# OSO-ALMO-A1-01.net
KiCad netlist of a schematic drawn in EAGLE
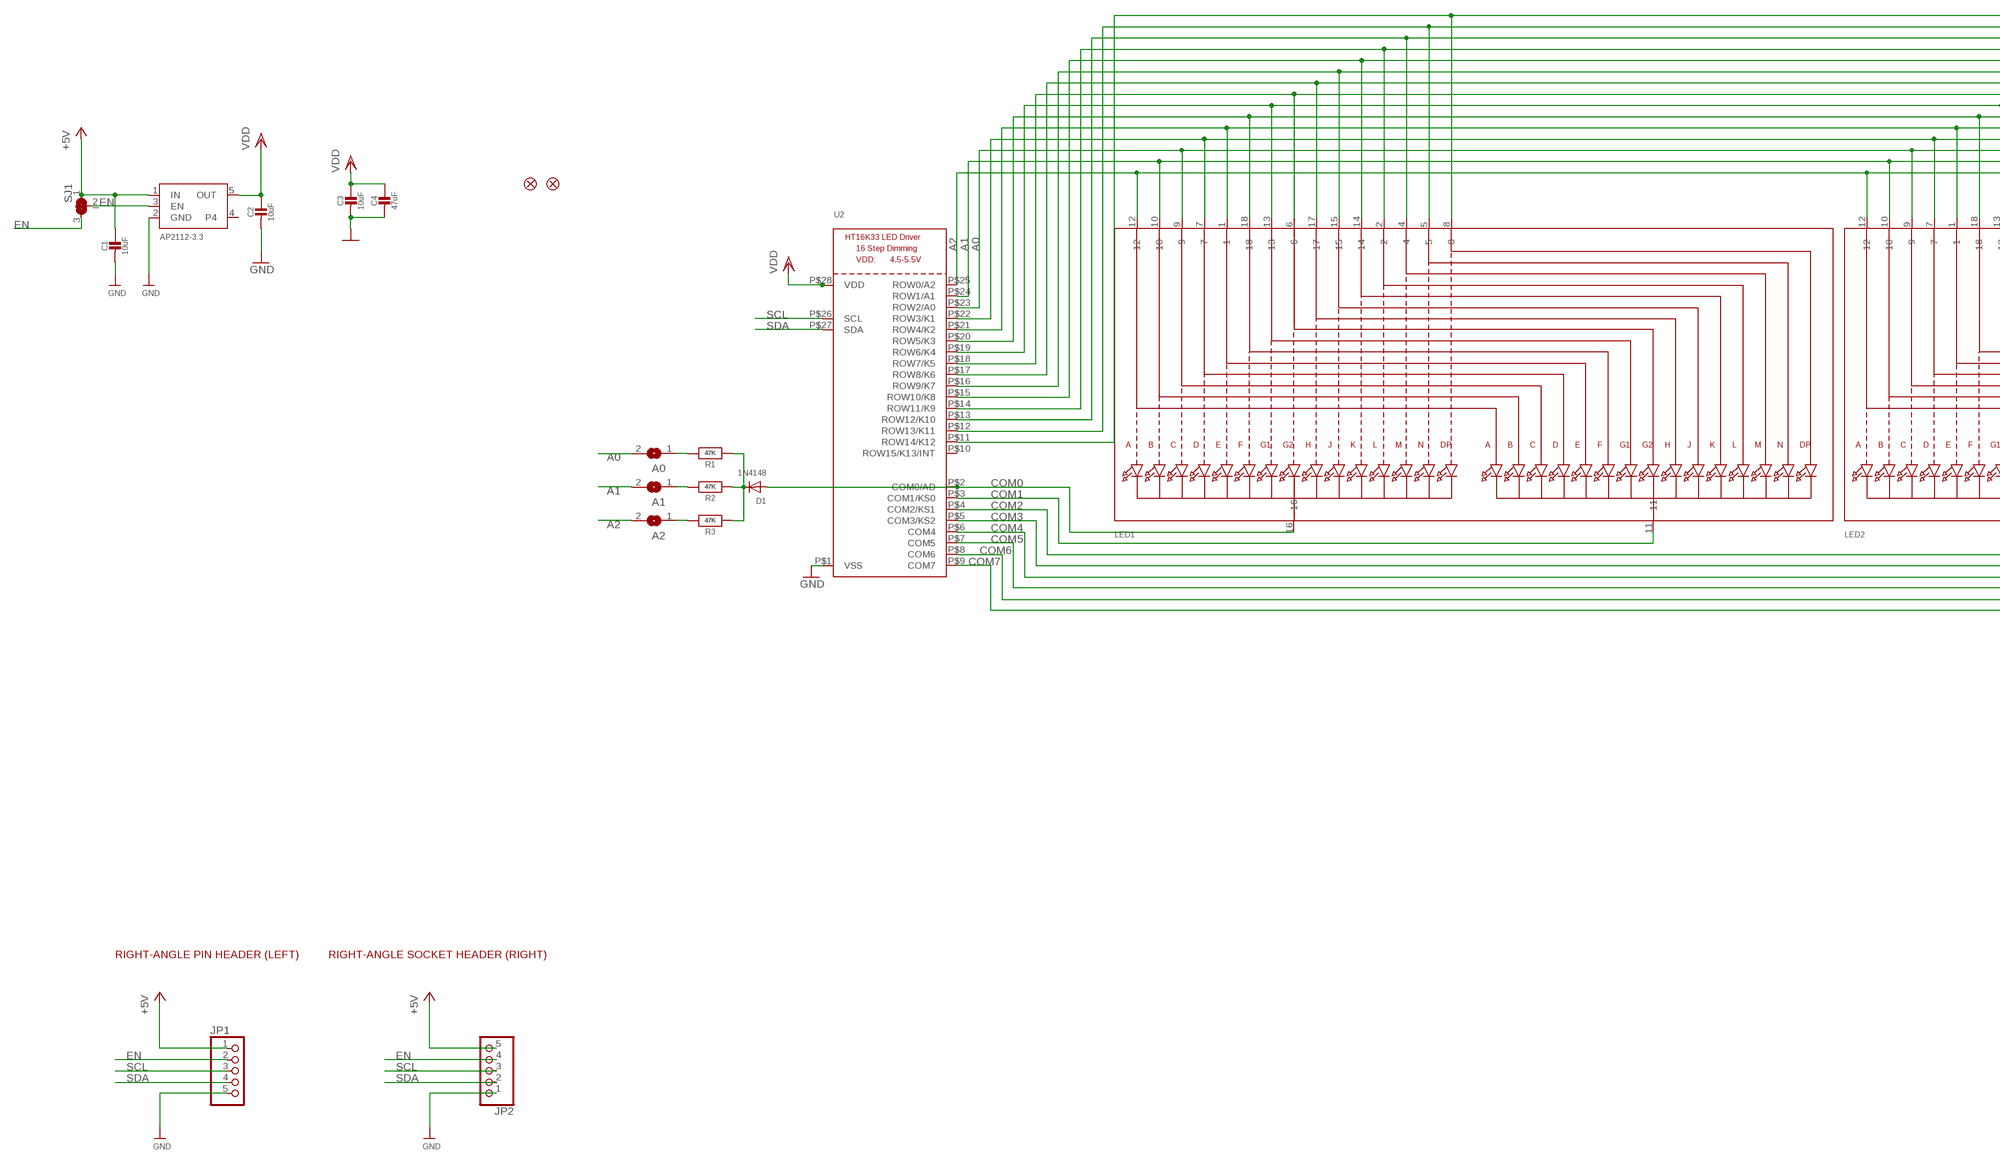
[diagram p0: schematic, sheet 1, part 1 of 2]
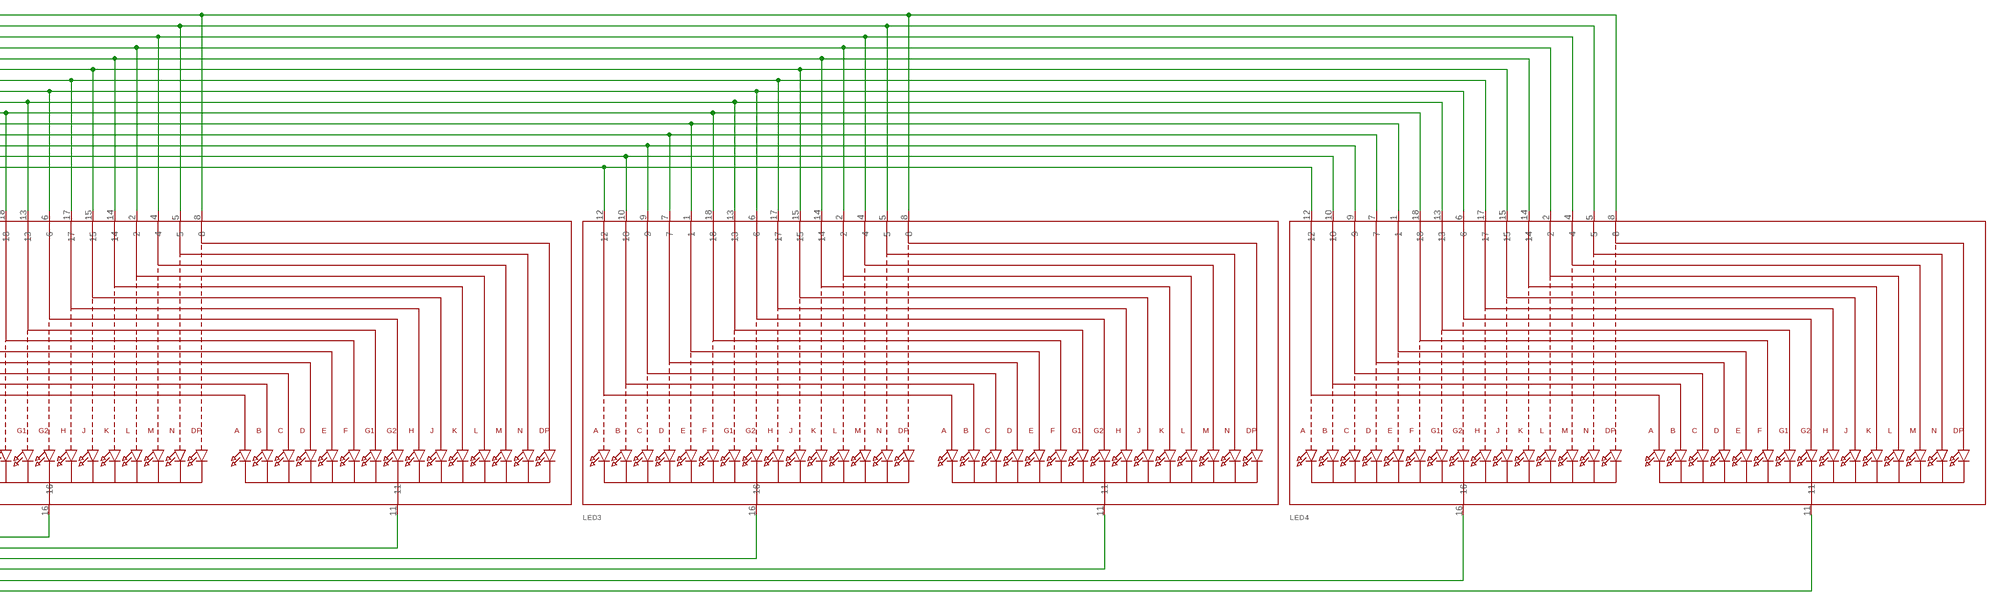
[diagram p1: schematic, sheet 1, part 2 of 2]

(export (version "E")
  (design (tool "Eeschema 10.0.6"))
  (components
    (comp (ref "A0")
      (value "SOLDERJUMPERREFLOW_NOPASTE")
      (footprint "eagle-import:SOLDERJUMPER_REFLOW_NOPASTE")
      (libsource (lib "eagle-import") (part "SOLDERJUMPERREFLOW_NOPASTE"))
    )
    (comp (ref "A1")
      (value "SOLDERJUMPERREFLOW_NOPASTE")
      (footprint "eagle-import:SOLDERJUMPER_REFLOW_NOPASTE")
      (libsource (lib "eagle-import") (part "SOLDERJUMPERREFLOW_NOPASTE"))
    )
    (comp (ref "A2")
      (value "SOLDERJUMPERREFLOW_NOPASTE")
      (footprint "eagle-import:SOLDERJUMPER_REFLOW_NOPASTE")
      (libsource (lib "eagle-import") (part "SOLDERJUMPERREFLOW_NOPASTE"))
    )
    (comp (ref "C1")
      (value "10uF")
      (footprint "eagle-import:0805-NO")
      (libsource (lib "eagle-import") (part "CAP_CERAMIC0805-NOOUTLINE"))
    )
    (comp (ref "C2")
      (value "10uF")
      (footprint "eagle-import:0805-NO")
      (libsource (lib "eagle-import") (part "CAP_CERAMIC0805-NOOUTLINE"))
    )
    (comp (ref "C3")
      (value "10uF")
      (footprint "eagle-import:0805-NO")
      (libsource (lib "eagle-import") (part "CAP_CERAMIC0805-NOOUTLINE"))
    )
    (comp (ref "C4")
      (value "47uF")
      (footprint "eagle-import:0805-NO")
      (libsource (lib "eagle-import") (part "CAP_CERAMIC0805-NOOUTLINE"))
    )
    (comp (ref "D1")
      (value "1N4148")
      (footprint "eagle-import:SOD-123FL")
      (libsource (lib "eagle-import") (part "DIODE_SOD-123FL"))
    )
    (comp (ref "JP1")
      (value "PINHD-1X5/90")
      (footprint "eagle-import:1X05_90")
      (libsource (lib "eagle-import") (part "PINHD-1X5/90"))
    )
    (comp (ref "JP2")
      (value "PINHD-1X5/90")
      (footprint "eagle-import:1X05_90")
      (libsource (lib "eagle-import") (part "PINHD-1X5/90"))
    )
    (comp (ref "LED1")
      (value "DISP_SEGMENT_STARBURST_DUAL_COMMONCATHODE")
      (footprint "eagle-import:SEGMENT_STARTBUST_DUAL_KWA-541CBB")
      (libsource (lib "eagle-import") (part "DISP_SEGMENT_STARBURST_DUAL_COMMONCATHODE"))
    )
    (comp (ref "LED2")
      (value "DISP_SEGMENT_STARBURST_DUAL_COMMONCATHODE")
      (footprint "eagle-import:SEGMENT_STARTBUST_DUAL_KWA-541CBB")
      (libsource (lib "eagle-import") (part "DISP_SEGMENT_STARBURST_DUAL_COMMONCATHODE"))
    )
    (comp (ref "LED3")
      (value "DISP_SEGMENT_STARBURST_DUAL_COMMONCATHODE")
      (footprint "eagle-import:SEGMENT_STARTBUST_DUAL_KWA-541CBB")
      (libsource (lib "eagle-import") (part "DISP_SEGMENT_STARBURST_DUAL_COMMONCATHODE"))
    )
    (comp (ref "LED4")
      (value "DISP_SEGMENT_STARBURST_DUAL_COMMONCATHODE")
      (footprint "eagle-import:SEGMENT_STARTBUST_DUAL_KWA-541CBB")
      (libsource (lib "eagle-import") (part "DISP_SEGMENT_STARBURST_DUAL_COMMONCATHODE"))
    )
    (comp (ref "R1")
      (value "47K")
      (footprint "eagle-import:0805-NO")
      (libsource (lib "eagle-import") (part "RESISTOR0805_NOOUTLINE"))
    )
    (comp (ref "R2")
      (value "47K")
      (footprint "eagle-import:0805-NO")
      (libsource (lib "eagle-import") (part "RESISTOR0805_NOOUTLINE"))
    )
    (comp (ref "R3")
      (value "47K")
      (footprint "eagle-import:0805-NO")
      (libsource (lib "eagle-import") (part "RESISTOR0805_NOOUTLINE"))
    )
    (comp (ref "SJ1")
      (value "SOLDERJUMPER_2WAY")
      (footprint "eagle-import:SOLDERJUMPER_2WAY_OPEN_NOPASTE")
      (libsource (lib "eagle-import") (part "SOLDERJUMPER_2WAY"))
    )
    (comp (ref "U$1")
      (value "FIDUCIAL\"\"")
      (footprint "eagle-import:FIDUCIAL_1MM")
      (libsource (lib "eagle-import") (part "FIDUCIAL{dblquote}{dblquote}"))
    )
    (comp (ref "U$2")
      (value "FIDUCIAL\"\"")
      (footprint "eagle-import:FIDUCIAL_1MM")
      (libsource (lib "eagle-import") (part "FIDUCIAL{dblquote}{dblquote}"))
    )
    (comp (ref "U1")
      (value "AP2112-3.3")
      (footprint "eagle-import:SOT23-5")
      (libsource (lib "eagle-import") (part "VREG_SOT23-5"))
    )
    (comp (ref "U2")
      (value "HT16K33_SOP28_SKINNY")
      (footprint "eagle-import:SOP28_300MIL_SKINNY")
      (libsource (lib "eagle-import") (part "HT16K33_SOP28_SKINNY"))
    )
  )
  (nets
    (net (code "1") (name "+5V") (class "Default")
      (node (ref "C1") (pin "1") (pinfunction "1_1") (pintype "passive"))
      (node (ref "JP1") (pin "1") (pinfunction "1_1") (pintype "passive"))
      (node (ref "JP2") (pin "5") (pinfunction "5_5") (pintype "passive"))
      (node (ref "SJ1") (pin "1") (pinfunction "1_1") (pintype "passive"))
      (node (ref "U1") (pin "1") (pinfunction "IN_1") (pintype "power_in"))
    )
    (net (code "2") (name "/A0") (class "Default")
      (node (ref "A0") (pin "2") (pinfunction "2_2") (pintype "passive"))
      (node (ref "LED1") (pin "9") (pinfunction "9_9") (pintype "bidirectional"))
      (node (ref "LED2") (pin "9") (pinfunction "9_9") (pintype "bidirectional"))
      (node (ref "LED3") (pin "9") (pinfunction "9_9") (pintype "bidirectional"))
      (node (ref "LED4") (pin "9") (pinfunction "9_9") (pintype "bidirectional"))
      (node (ref "U2") (pin "P$23") (pinfunction "ROW2/A0_P$23") (pintype "bidirectional"))
    )
    (net (code "3") (name "/A1") (class "Default")
      (node (ref "A1") (pin "2") (pinfunction "2_2") (pintype "passive"))
      (node (ref "LED1") (pin "10") (pinfunction "10_10") (pintype "bidirectional"))
      (node (ref "LED2") (pin "10") (pinfunction "10_10") (pintype "bidirectional"))
      (node (ref "LED3") (pin "10") (pinfunction "10_10") (pintype "bidirectional"))
      (node (ref "LED4") (pin "10") (pinfunction "10_10") (pintype "bidirectional"))
      (node (ref "U2") (pin "P$24") (pinfunction "ROW1/A1_P$24") (pintype "bidirectional"))
    )
    (net (code "4") (name "/A2") (class "Default")
      (node (ref "A2") (pin "2") (pinfunction "2_2") (pintype "passive"))
      (node (ref "LED1") (pin "12") (pinfunction "12_12") (pintype "bidirectional"))
      (node (ref "LED2") (pin "12") (pinfunction "12_12") (pintype "bidirectional"))
      (node (ref "LED3") (pin "12") (pinfunction "12_12") (pintype "bidirectional"))
      (node (ref "LED4") (pin "12") (pinfunction "12_12") (pintype "bidirectional"))
      (node (ref "U2") (pin "P$25") (pinfunction "ROW0/A2_P$25") (pintype "bidirectional"))
    )
    (net (code "5") (name "/COM0") (class "Default")
      (node (ref "D1") (pin "A") (pinfunction "A_A") (pintype "passive"))
      (node (ref "LED1") (pin "16") (pinfunction "16_16") (pintype "bidirectional"))
      (node (ref "U2") (pin "P$2") (pinfunction "COM0/AD_P$2") (pintype "bidirectional"))
    )
    (net (code "6") (name "/COM1") (class "Default")
      (node (ref "LED1") (pin "11") (pinfunction "11_11") (pintype "bidirectional"))
      (node (ref "U2") (pin "P$3") (pinfunction "COM1/KS0_P$3") (pintype "bidirectional"))
    )
    (net (code "7") (name "/COM2") (class "Default")
      (node (ref "LED2") (pin "16") (pinfunction "16_16") (pintype "bidirectional"))
      (node (ref "U2") (pin "P$4") (pinfunction "COM2/KS1_P$4") (pintype "bidirectional"))
    )
    (net (code "8") (name "/COM3") (class "Default")
      (node (ref "LED2") (pin "11") (pinfunction "11_11") (pintype "bidirectional"))
      (node (ref "U2") (pin "P$5") (pinfunction "COM3/KS2_P$5") (pintype "bidirectional"))
    )
    (net (code "9") (name "/COM4") (class "Default")
      (node (ref "LED3") (pin "16") (pinfunction "16_16") (pintype "bidirectional"))
      (node (ref "U2") (pin "P$6") (pinfunction "COM4_P$6") (pintype "bidirectional"))
    )
    (net (code "10") (name "/COM5") (class "Default")
      (node (ref "LED3") (pin "11") (pinfunction "11_11") (pintype "bidirectional"))
      (node (ref "U2") (pin "P$7") (pinfunction "COM5_P$7") (pintype "bidirectional"))
    )
    (net (code "11") (name "/COM6") (class "Default")
      (node (ref "LED4") (pin "16") (pinfunction "16_16") (pintype "bidirectional"))
      (node (ref "U2") (pin "P$8") (pinfunction "COM6_P$8") (pintype "bidirectional"))
    )
    (net (code "12") (name "/COM7") (class "Default")
      (node (ref "LED4") (pin "11") (pinfunction "11_11") (pintype "bidirectional"))
      (node (ref "U2") (pin "P$9") (pinfunction "COM7_P$9") (pintype "bidirectional"))
    )
    (net (code "13") (name "/EN") (class "Default")
      (node (ref "JP1") (pin "2") (pinfunction "2_2") (pintype "passive"))
      (node (ref "JP2") (pin "4") (pinfunction "4_4") (pintype "passive"))
      (node (ref "SJ1") (pin "3") (pinfunction "3_3") (pintype "passive"))
    )
    (net (code "14") (name "/SCL") (class "Default")
      (node (ref "JP1") (pin "3") (pinfunction "3_3") (pintype "passive"))
      (node (ref "JP2") (pin "3") (pinfunction "3_3") (pintype "passive"))
      (node (ref "U2") (pin "P$26") (pinfunction "SCL_P$26") (pintype "bidirectional"))
    )
    (net (code "15") (name "/SDA") (class "Default")
      (node (ref "JP1") (pin "4") (pinfunction "4_4") (pintype "passive"))
      (node (ref "JP2") (pin "2") (pinfunction "2_2") (pintype "passive"))
      (node (ref "U2") (pin "P$27") (pinfunction "SDA_P$27") (pintype "bidirectional"))
    )
    (net (code "16") (name "/_EN") (class "Default")
      (node (ref "SJ1") (pin "2") (pinfunction "2_2") (pintype "passive"))
      (node (ref "U1") (pin "3") (pinfunction "EN_3") (pintype "input"))
    )
    (net (code "17") (name "GND") (class "Default")
      (node (ref "C1") (pin "2") (pinfunction "2_2") (pintype "passive"))
      (node (ref "C2") (pin "2") (pinfunction "2_2") (pintype "passive"))
      (node (ref "C3") (pin "2") (pinfunction "2_2") (pintype "passive"))
      (node (ref "C4") (pin "2") (pinfunction "2_2") (pintype "passive"))
      (node (ref "JP1") (pin "5") (pinfunction "5_5") (pintype "passive"))
      (node (ref "JP2") (pin "1") (pinfunction "1_1") (pintype "passive"))
      (node (ref "U1") (pin "2") (pinfunction "GND_2") (pintype "power_in"))
      (node (ref "U2") (pin "P$1") (pinfunction "VSS_P$1") (pintype "bidirectional"))
    )
    (net (code "18") (name "Net-(A0-Pad1)") (class "Default")
      (node (ref "A0") (pin "1") (pinfunction "1_1") (pintype "passive"))
      (node (ref "R1") (pin "2") (pinfunction "2_2") (pintype "passive"))
    )
    (net (code "19") (name "Net-(A1-Pad1)") (class "Default")
      (node (ref "A1") (pin "1") (pinfunction "1_1") (pintype "passive"))
      (node (ref "R2") (pin "2") (pinfunction "2_2") (pintype "passive"))
    )
    (net (code "20") (name "Net-(A2-Pad1)") (class "Default")
      (node (ref "A2") (pin "1") (pinfunction "1_1") (pintype "passive"))
      (node (ref "R3") (pin "2") (pinfunction "2_2") (pintype "passive"))
    )
    (net (code "21") (name "Net-(D1-PadC)") (class "Default")
      (node (ref "D1") (pin "C") (pinfunction "C_C") (pintype "passive"))
      (node (ref "R1") (pin "1") (pinfunction "1_1") (pintype "passive"))
      (node (ref "R2") (pin "1") (pinfunction "1_1") (pintype "passive"))
      (node (ref "R3") (pin "1") (pinfunction "1_1") (pintype "passive"))
    )
    (net (code "22") (name "Net-(U2-ROW3{slash}K1)") (class "Default")
      (node (ref "LED1") (pin "7") (pinfunction "7_7") (pintype "bidirectional"))
      (node (ref "LED2") (pin "7") (pinfunction "7_7") (pintype "bidirectional"))
      (node (ref "LED3") (pin "7") (pinfunction "7_7") (pintype "bidirectional"))
      (node (ref "LED4") (pin "7") (pinfunction "7_7") (pintype "bidirectional"))
      (node (ref "U2") (pin "P$22") (pinfunction "ROW3/K1_P$22") (pintype "bidirectional"))
    )
    (net (code "23") (name "Net-(U2-ROW4{slash}K2)") (class "Default")
      (node (ref "LED1") (pin "1") (pinfunction "1_1") (pintype "bidirectional"))
      (node (ref "LED2") (pin "1") (pinfunction "1_1") (pintype "bidirectional"))
      (node (ref "LED3") (pin "1") (pinfunction "1_1") (pintype "bidirectional"))
      (node (ref "LED4") (pin "1") (pinfunction "1_1") (pintype "bidirectional"))
      (node (ref "U2") (pin "P$21") (pinfunction "ROW4/K2_P$21") (pintype "bidirectional"))
    )
    (net (code "24") (name "Net-(U2-ROW5{slash}K3)") (class "Default")
      (node (ref "LED1") (pin "18") (pinfunction "18_18") (pintype "bidirectional"))
      (node (ref "LED2") (pin "18") (pinfunction "18_18") (pintype "bidirectional"))
      (node (ref "LED3") (pin "18") (pinfunction "18_18") (pintype "bidirectional"))
      (node (ref "LED4") (pin "18") (pinfunction "18_18") (pintype "bidirectional"))
      (node (ref "U2") (pin "P$20") (pinfunction "ROW5/K3_P$20") (pintype "bidirectional"))
    )
    (net (code "25") (name "Net-(U2-ROW6{slash}K4)") (class "Default")
      (node (ref "LED1") (pin "13") (pinfunction "13_13") (pintype "bidirectional"))
      (node (ref "LED2") (pin "13") (pinfunction "13_13") (pintype "bidirectional"))
      (node (ref "LED3") (pin "13") (pinfunction "13_13") (pintype "bidirectional"))
      (node (ref "LED4") (pin "13") (pinfunction "13_13") (pintype "bidirectional"))
      (node (ref "U2") (pin "P$19") (pinfunction "ROW6/K4_P$19") (pintype "bidirectional"))
    )
    (net (code "26") (name "Net-(U2-ROW7{slash}K5)") (class "Default")
      (node (ref "LED1") (pin "6") (pinfunction "6_6") (pintype "bidirectional"))
      (node (ref "LED2") (pin "6") (pinfunction "6_6") (pintype "bidirectional"))
      (node (ref "LED3") (pin "6") (pinfunction "6_6") (pintype "bidirectional"))
      (node (ref "LED4") (pin "6") (pinfunction "6_6") (pintype "bidirectional"))
      (node (ref "U2") (pin "P$18") (pinfunction "ROW7/K5_P$18") (pintype "bidirectional"))
    )
    (net (code "27") (name "Net-(U2-ROW8{slash}K6)") (class "Default")
      (node (ref "LED1") (pin "17") (pinfunction "17_17") (pintype "bidirectional"))
      (node (ref "LED2") (pin "17") (pinfunction "17_17") (pintype "bidirectional"))
      (node (ref "LED3") (pin "17") (pinfunction "17_17") (pintype "bidirectional"))
      (node (ref "LED4") (pin "17") (pinfunction "17_17") (pintype "bidirectional"))
      (node (ref "U2") (pin "P$17") (pinfunction "ROW8/K6_P$17") (pintype "bidirectional"))
    )
    (net (code "28") (name "Net-(U2-ROW9{slash}K7)") (class "Default")
      (node (ref "LED1") (pin "15") (pinfunction "15_15") (pintype "bidirectional"))
      (node (ref "LED2") (pin "15") (pinfunction "15_15") (pintype "bidirectional"))
      (node (ref "LED3") (pin "15") (pinfunction "15_15") (pintype "bidirectional"))
      (node (ref "LED4") (pin "15") (pinfunction "15_15") (pintype "bidirectional"))
      (node (ref "U2") (pin "P$16") (pinfunction "ROW9/K7_P$16") (pintype "bidirectional"))
    )
    (net (code "29") (name "Net-(U2-ROW10{slash}K8)") (class "Default")
      (node (ref "LED1") (pin "14") (pinfunction "14_14") (pintype "bidirectional"))
      (node (ref "LED2") (pin "14") (pinfunction "14_14") (pintype "bidirectional"))
      (node (ref "LED3") (pin "14") (pinfunction "14_14") (pintype "bidirectional"))
      (node (ref "LED4") (pin "14") (pinfunction "14_14") (pintype "bidirectional"))
      (node (ref "U2") (pin "P$15") (pinfunction "ROW10/K8_P$15") (pintype "bidirectional"))
    )
    (net (code "30") (name "Net-(U2-ROW11{slash}K9)") (class "Default")
      (node (ref "LED1") (pin "2") (pinfunction "2_2") (pintype "bidirectional"))
      (node (ref "LED2") (pin "2") (pinfunction "2_2") (pintype "bidirectional"))
      (node (ref "LED3") (pin "2") (pinfunction "2_2") (pintype "bidirectional"))
      (node (ref "LED4") (pin "2") (pinfunction "2_2") (pintype "bidirectional"))
      (node (ref "U2") (pin "P$14") (pinfunction "ROW11/K9_P$14") (pintype "bidirectional"))
    )
    (net (code "31") (name "Net-(U2-ROW12{slash}K10)") (class "Default")
      (node (ref "LED1") (pin "4") (pinfunction "4_4") (pintype "bidirectional"))
      (node (ref "LED2") (pin "4") (pinfunction "4_4") (pintype "bidirectional"))
      (node (ref "LED3") (pin "4") (pinfunction "4_4") (pintype "bidirectional"))
      (node (ref "LED4") (pin "4") (pinfunction "4_4") (pintype "bidirectional"))
      (node (ref "U2") (pin "P$13") (pinfunction "ROW12/K10_P$13") (pintype "bidirectional"))
    )
    (net (code "32") (name "Net-(U2-ROW13{slash}K11)") (class "Default")
      (node (ref "LED1") (pin "5") (pinfunction "5_5") (pintype "bidirectional"))
      (node (ref "LED2") (pin "5") (pinfunction "5_5") (pintype "bidirectional"))
      (node (ref "LED3") (pin "5") (pinfunction "5_5") (pintype "bidirectional"))
      (node (ref "LED4") (pin "5") (pinfunction "5_5") (pintype "bidirectional"))
      (node (ref "U2") (pin "P$12") (pinfunction "ROW13/K11_P$12") (pintype "bidirectional"))
    )
    (net (code "33") (name "Net-(U2-ROW14{slash}K12)") (class "Default")
      (node (ref "LED1") (pin "8") (pinfunction "8_8") (pintype "bidirectional"))
      (node (ref "LED2") (pin "8") (pinfunction "8_8") (pintype "bidirectional"))
      (node (ref "LED3") (pin "8") (pinfunction "8_8") (pintype "bidirectional"))
      (node (ref "LED4") (pin "8") (pinfunction "8_8") (pintype "bidirectional"))
      (node (ref "U2") (pin "P$11") (pinfunction "ROW14/K12_P$11") (pintype "bidirectional"))
    )
    (net (code "34") (name "VDD") (class "Default")
      (node (ref "C2") (pin "1") (pinfunction "1_1") (pintype "passive"))
      (node (ref "C3") (pin "1") (pinfunction "1_1") (pintype "passive"))
      (node (ref "C4") (pin "1") (pinfunction "1_1") (pintype "passive"))
      (node (ref "U1") (pin "5") (pinfunction "OUT_5") (pintype "power_in"))
      (node (ref "U2") (pin "P$28") (pinfunction "VDD_P$28") (pintype "bidirectional"))
    )
    (net (code "35") (name "unconnected-(U1-P4-Pad4)") (class "Default")
      (node (ref "U1") (pin "4") (pinfunction "P4_4") (pintype "bidirectional"))
    )
    (net (code "36") (name "unconnected-(U2-ROW15{slash}K13{slash}INT-PadP$10)") (class "Default")
      (node (ref "U2") (pin "P$10") (pinfunction "ROW15/K13/INT_P$10") (pintype "bidirectional"))
    )
  )
)
